# tgam_breakout.net
KiCad netlist of a schematic drawn in EAGLE
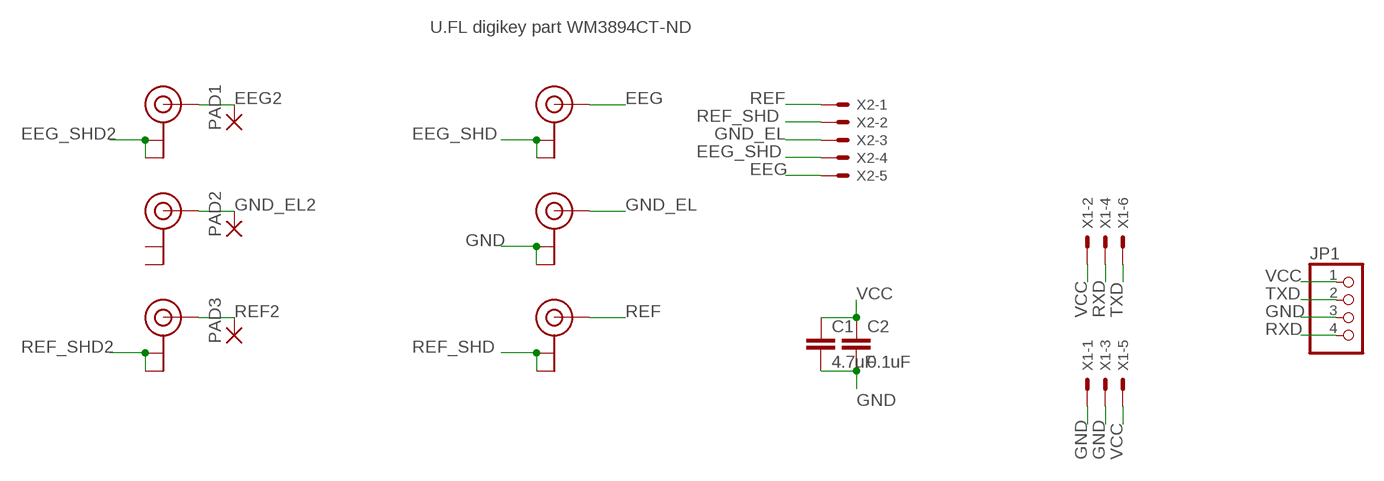
[diagram p0: schematic, sheet 1]

(export (version "E")
  (design (tool "Eeschema 10.0.6"))
  (components
    (comp (ref "C1")
      (value "4.7uF")
      (footprint "eagle-import:C0805")
      (libsource (lib "eagle-import") (part "C-EUC0805"))
    )
    (comp (ref "C2")
      (value "0.1uF")
      (footprint "eagle-import:C0805")
      (libsource (lib "eagle-import") (part "C-EUC0805"))
    )
    (comp (ref "EEG")
      (value "U.FL")
      (footprint "eagle-import:U.FL")
      (libsource (lib "eagle-import") (part "U.FL"))
    )
    (comp (ref "EEG_EL")
      (value "U.FL")
      (footprint "eagle-import:U.FL")
      (libsource (lib "eagle-import") (part "U.FL"))
    )
    (comp (ref "GND_EL")
      (value "U.FL")
      (footprint "eagle-import:U.FL")
      (libsource (lib "eagle-import") (part "U.FL"))
    )
    (comp (ref "GND_ELEL")
      (value "U.FL")
      (footprint "eagle-import:U.FL")
      (libsource (lib "eagle-import") (part "U.FL"))
    )
    (comp (ref "JP1")
      (value "PINHD-1X4")
      (footprint "eagle-import:1X04")
      (libsource (lib "eagle-import") (part "PINHD-1X4"))
    )
    (comp (ref "PAD1")
      (value "SMD5")
      (footprint "eagle-import:SMD2,54-5,08")
      (libsource (lib "eagle-import") (part "SMD5"))
    )
    (comp (ref "PAD2")
      (value "SMD5")
      (footprint "eagle-import:SMD2,54-5,08")
      (libsource (lib "eagle-import") (part "SMD5"))
    )
    (comp (ref "PAD3")
      (value "SMD5")
      (footprint "eagle-import:SMD2,54-5,08")
      (libsource (lib "eagle-import") (part "SMD5"))
    )
    (comp (ref "REF")
      (value "U.FL")
      (footprint "eagle-import:U.FL")
      (libsource (lib "eagle-import") (part "U.FL"))
    )
    (comp (ref "REF_EL")
      (value "U.FL")
      (footprint "eagle-import:U.FL")
      (libsource (lib "eagle-import") (part "U.FL"))
    )
    (comp (ref "X1")
      (value "332-06")
      (footprint "eagle-import:332-06")
      (libsource (lib "eagle-import") (part "332-06"))
    )
    (comp (ref "X2")
      (value "332-10")
      (footprint "eagle-import:2MM5SIL")
      (libsource (lib "eagle-import") (part "332-10"))
    )
  )
  (nets
    (net (code "1") (name "/EEG") (class "Default")
      (node (ref "EEG") (pin "P$3") (pinfunction "SIGNAL_P$3") (pintype "bidirectional"))
      (node (ref "X2") (pin "9") (pinfunction "S_9") (pintype "passive"))
    )
    (net (code "2") (name "/EEG2") (class "Default")
      (node (ref "EEG_EL") (pin "P$3") (pinfunction "SIGNAL_P$3") (pintype "bidirectional"))
      (node (ref "PAD1") (pin "1") (pinfunction "P_1") (pintype "passive"))
    )
    (net (code "3") (name "/EEG_SHD") (class "Default")
      (node (ref "EEG") (pin "P$1") (pinfunction "GND_P$1") (pintype "bidirectional"))
      (node (ref "EEG") (pin "P$2") (pinfunction "GND_P$2") (pintype "bidirectional"))
      (node (ref "X2") (pin "7") (pinfunction "S_7") (pintype "passive"))
    )
    (net (code "4") (name "/EEG_SHD2") (class "Default")
      (node (ref "EEG_EL") (pin "P$1") (pinfunction "GND_P$1") (pintype "bidirectional"))
      (node (ref "EEG_EL") (pin "P$2") (pinfunction "GND_P$2") (pintype "bidirectional"))
    )
    (net (code "5") (name "/GND") (class "Default")
      (node (ref "C1") (pin "2") (pinfunction "2_2") (pintype "passive"))
      (node (ref "C2") (pin "2") (pinfunction "2_2") (pintype "passive"))
      (node (ref "GND_EL") (pin "P$1") (pinfunction "GND_P$1") (pintype "bidirectional"))
      (node (ref "GND_EL") (pin "P$2") (pinfunction "GND_P$2") (pintype "bidirectional"))
      (node (ref "JP1") (pin "3") (pinfunction "3_3") (pintype "passive"))
      (node (ref "X1") (pin "1") (pinfunction "S_1") (pintype "passive"))
      (node (ref "X1") (pin "3") (pinfunction "S_3") (pintype "passive"))
    )
    (net (code "6") (name "/GND_EL") (class "Default")
      (node (ref "GND_EL") (pin "P$3") (pinfunction "SIGNAL_P$3") (pintype "bidirectional"))
      (node (ref "X2") (pin "5") (pinfunction "S_5") (pintype "passive"))
    )
    (net (code "7") (name "/GND_EL2") (class "Default")
      (node (ref "GND_ELEL") (pin "P$3") (pinfunction "SIGNAL_P$3") (pintype "bidirectional"))
      (node (ref "PAD2") (pin "1") (pinfunction "P_1") (pintype "passive"))
    )
    (net (code "8") (name "/REF") (class "Default")
      (node (ref "REF") (pin "P$3") (pinfunction "SIGNAL_P$3") (pintype "bidirectional"))
      (node (ref "X2") (pin "1") (pinfunction "S_1") (pintype "passive"))
    )
    (net (code "9") (name "/REF2") (class "Default")
      (node (ref "PAD3") (pin "1") (pinfunction "P_1") (pintype "passive"))
      (node (ref "REF_EL") (pin "P$3") (pinfunction "SIGNAL_P$3") (pintype "bidirectional"))
    )
    (net (code "10") (name "/REF_SHD") (class "Default")
      (node (ref "REF") (pin "P$1") (pinfunction "GND_P$1") (pintype "bidirectional"))
      (node (ref "REF") (pin "P$2") (pinfunction "GND_P$2") (pintype "bidirectional"))
      (node (ref "X2") (pin "3") (pinfunction "S_3") (pintype "passive"))
    )
    (net (code "11") (name "/REF_SHD2") (class "Default")
      (node (ref "REF_EL") (pin "P$1") (pinfunction "GND_P$1") (pintype "bidirectional"))
      (node (ref "REF_EL") (pin "P$2") (pinfunction "GND_P$2") (pintype "bidirectional"))
    )
    (net (code "12") (name "/RXD") (class "Default")
      (node (ref "JP1") (pin "4") (pinfunction "4_4") (pintype "passive"))
      (node (ref "X1") (pin "4") (pinfunction "S_4") (pintype "passive"))
    )
    (net (code "13") (name "/TXD") (class "Default")
      (node (ref "JP1") (pin "2") (pinfunction "2_2") (pintype "passive"))
      (node (ref "X1") (pin "6") (pinfunction "S_6") (pintype "passive"))
    )
    (net (code "14") (name "/VCC") (class "Default")
      (node (ref "C1") (pin "1") (pinfunction "1_1") (pintype "passive"))
      (node (ref "C2") (pin "1") (pinfunction "1_1") (pintype "passive"))
      (node (ref "JP1") (pin "1") (pinfunction "1_1") (pintype "passive"))
      (node (ref "X1") (pin "2") (pinfunction "S_2") (pintype "passive"))
      (node (ref "X1") (pin "5") (pinfunction "S_5") (pintype "passive"))
    )
    (net (code "15") (name "unconnected-(GND_ELEL-GND-PadP$1)") (class "Default")
      (node (ref "GND_ELEL") (pin "P$1") (pinfunction "GND_P$1") (pintype "bidirectional"))
    )
    (net (code "16") (name "unconnected-(GND_ELEL-GND-PadP$2)") (class "Default")
      (node (ref "GND_ELEL") (pin "P$2") (pinfunction "GND_P$2") (pintype "bidirectional"))
    )
  )
)
